# rx_mod-1.net
KiCad netlist of a schematic drawn in EAGLE
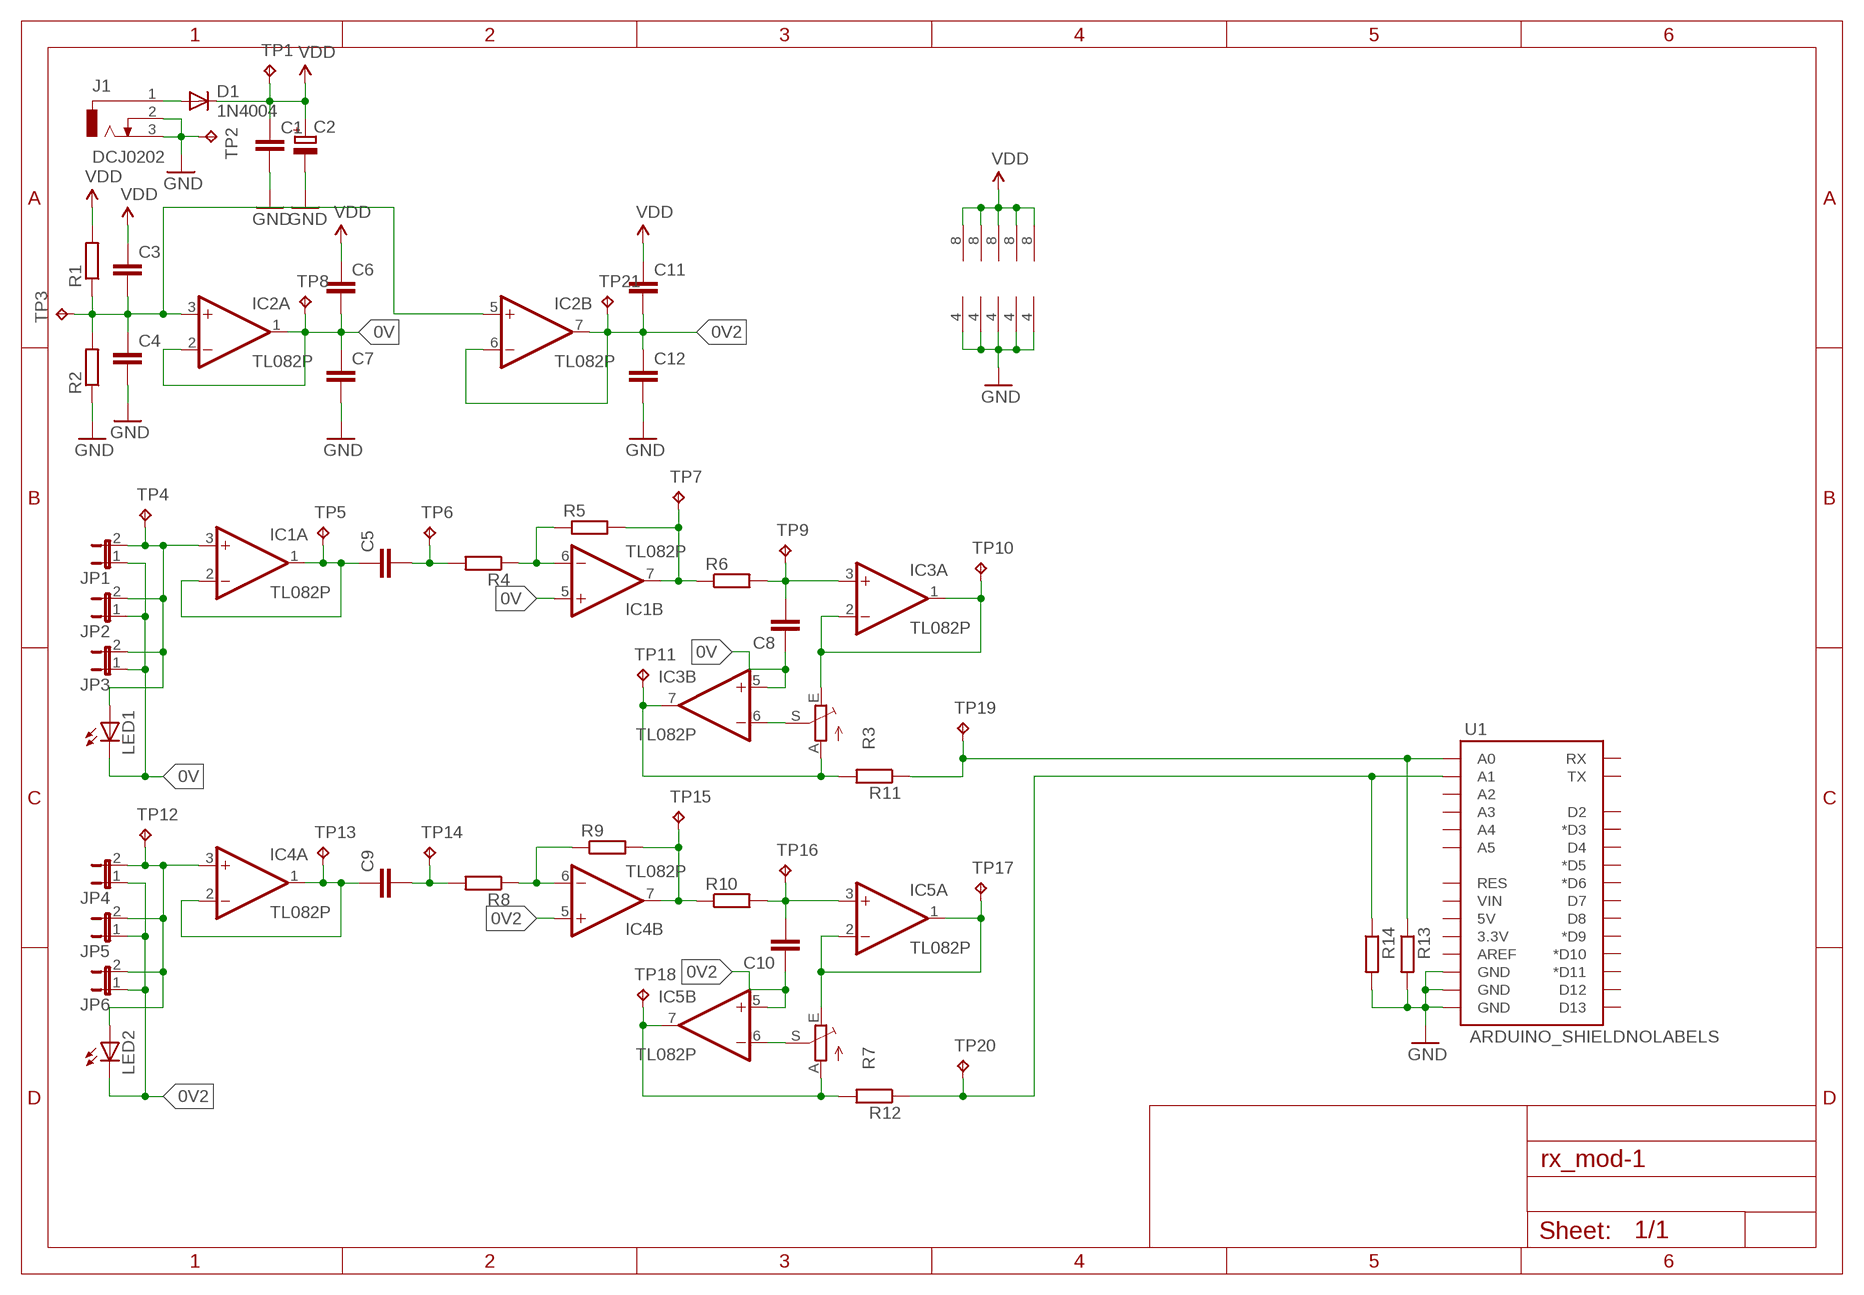
[diagram p0: schematic, sheet 1]

(export (version "E")
  (design (tool "Eeschema 10.0.6"))
  (components
    (comp (ref "C1")
      (value "C-EU050-030X075")
      (footprint "eagle-import:C050-030X075")
      (libsource (lib "eagle-import") (part "C-EU050-030X075"))
    )
    (comp (ref "C2")
      (value "CPOL-EUE2.5-6")
      (footprint "eagle-import:E2,5-6")
      (libsource (lib "eagle-import") (part "CPOL-EUE2.5-6"))
    )
    (comp (ref "C3")
      (value "C-EU050-030X075")
      (footprint "eagle-import:C050-030X075")
      (libsource (lib "eagle-import") (part "C-EU050-030X075"))
    )
    (comp (ref "C4")
      (value "C-EU050-030X075")
      (footprint "eagle-import:C050-030X075")
      (libsource (lib "eagle-import") (part "C-EU050-030X075"))
    )
    (comp (ref "C5")
      (value "C-EU050-030X075")
      (footprint "eagle-import:C050-030X075")
      (libsource (lib "eagle-import") (part "C-EU050-030X075"))
    )
    (comp (ref "C6")
      (value "C-EU050-030X075")
      (footprint "eagle-import:C050-030X075")
      (libsource (lib "eagle-import") (part "C-EU050-030X075"))
    )
    (comp (ref "C7")
      (value "C-EU050-030X075")
      (footprint "eagle-import:C050-030X075")
      (libsource (lib "eagle-import") (part "C-EU050-030X075"))
    )
    (comp (ref "C8")
      (value "C-EU050-030X075")
      (footprint "eagle-import:C050-030X075")
      (libsource (lib "eagle-import") (part "C-EU050-030X075"))
    )
    (comp (ref "C9")
      (value "C-EU050-030X075")
      (footprint "eagle-import:C050-030X075")
      (libsource (lib "eagle-import") (part "C-EU050-030X075"))
    )
    (comp (ref "C10")
      (value "C-EU050-030X075")
      (footprint "eagle-import:C050-030X075")
      (libsource (lib "eagle-import") (part "C-EU050-030X075"))
    )
    (comp (ref "C11")
      (value "C-EU050-030X075")
      (footprint "eagle-import:C050-030X075")
      (libsource (lib "eagle-import") (part "C-EU050-030X075"))
    )
    (comp (ref "C12")
      (value "C-EU050-030X075")
      (footprint "eagle-import:C050-030X075")
      (libsource (lib "eagle-import") (part "C-EU050-030X075"))
    )
    (comp (ref "D1")
      (value "1N4004")
      (footprint "eagle-import:DO41-10")
      (libsource (lib "eagle-import") (part "1N4004"))
    )
    (comp (ref "IC1")
      (value "TL082P")
      (footprint "eagle-import:DIL08")
      (libsource (lib "eagle-import") (part "TL082P"))
    )
    (comp (ref "IC2")
      (value "TL082P")
      (footprint "eagle-import:DIL08")
      (libsource (lib "eagle-import") (part "TL082P"))
    )
    (comp (ref "IC3")
      (value "TL082P")
      (footprint "eagle-import:DIL08")
      (libsource (lib "eagle-import") (part "TL082P"))
    )
    (comp (ref "IC4")
      (value "TL082P")
      (footprint "eagle-import:DIL08")
      (libsource (lib "eagle-import") (part "TL082P"))
    )
    (comp (ref "IC5")
      (value "TL082P")
      (footprint "eagle-import:DIL08")
      (libsource (lib "eagle-import") (part "TL082P"))
    )
    (comp (ref "J1")
      (value "DCJ0202")
      (footprint "eagle-import:DCJ0202")
      (libsource (lib "eagle-import") (part "DCJ0202"))
    )
    (comp (ref "JP1")
      (value "JP1E")
      (footprint "eagle-import:JP1")
      (libsource (lib "eagle-import") (part "JP1E"))
    )
    (comp (ref "JP2")
      (value "JP1E")
      (footprint "eagle-import:JP1")
      (libsource (lib "eagle-import") (part "JP1E"))
    )
    (comp (ref "JP3")
      (value "JP1E")
      (footprint "eagle-import:JP1")
      (libsource (lib "eagle-import") (part "JP1E"))
    )
    (comp (ref "JP4")
      (value "JP1E")
      (footprint "eagle-import:JP1")
      (libsource (lib "eagle-import") (part "JP1E"))
    )
    (comp (ref "JP5")
      (value "JP1E")
      (footprint "eagle-import:JP1")
      (libsource (lib "eagle-import") (part "JP1E"))
    )
    (comp (ref "JP6")
      (value "JP1E")
      (footprint "eagle-import:JP1")
      (libsource (lib "eagle-import") (part "JP1E"))
    )
    (comp (ref "LED1")
      (value "LED5MM")
      (footprint "eagle-import:LED5MM")
      (libsource (lib "eagle-import") (part "LED5MM"))
    )
    (comp (ref "LED2")
      (value "LED5MM")
      (footprint "eagle-import:LED5MM")
      (libsource (lib "eagle-import") (part "LED5MM"))
    )
    (comp (ref "R1")
      (value "R-EU_0207/10")
      (footprint "eagle-import:0207_10")
      (libsource (lib "eagle-import") (part "R-EU_0207/10"))
    )
    (comp (ref "R2")
      (value "R-EU_0207/10")
      (footprint "eagle-import:0207_10")
      (libsource (lib "eagle-import") (part "R-EU_0207/10"))
    )
    (comp (ref "R3")
      (value "TRIM_EU-CA9V")
      (footprint "eagle-import:CA9V")
      (libsource (lib "eagle-import") (part "TRIM_EU-CA9V"))
    )
    (comp (ref "R4")
      (value "R-EU_0207/10")
      (footprint "eagle-import:0207_10")
      (libsource (lib "eagle-import") (part "R-EU_0207/10"))
    )
    (comp (ref "R5")
      (value "R-EU_0207/2V")
      (footprint "eagle-import:0207_2V")
      (libsource (lib "eagle-import") (part "R-EU_0207/2V"))
    )
    (comp (ref "R6")
      (value "R-EU_0207/2V")
      (footprint "eagle-import:0207_2V")
      (libsource (lib "eagle-import") (part "R-EU_0207/2V"))
    )
    (comp (ref "R7")
      (value "TRIM_EU-CA9V")
      (footprint "eagle-import:CA9V")
      (libsource (lib "eagle-import") (part "TRIM_EU-CA9V"))
    )
    (comp (ref "R8")
      (value "R-EU_0207/10")
      (footprint "eagle-import:0207_10")
      (libsource (lib "eagle-import") (part "R-EU_0207/10"))
    )
    (comp (ref "R9")
      (value "R-EU_0207/2V")
      (footprint "eagle-import:0207_2V")
      (libsource (lib "eagle-import") (part "R-EU_0207/2V"))
    )
    (comp (ref "R10")
      (value "R-EU_0207/2V")
      (footprint "eagle-import:0207_2V")
      (libsource (lib "eagle-import") (part "R-EU_0207/2V"))
    )
    (comp (ref "R11")
      (value "R-EU_0207/10")
      (footprint "eagle-import:0207_10")
      (libsource (lib "eagle-import") (part "R-EU_0207/10"))
    )
    (comp (ref "R12")
      (value "R-EU_0207/10")
      (footprint "eagle-import:0207_10")
      (libsource (lib "eagle-import") (part "R-EU_0207/10"))
    )
    (comp (ref "R13")
      (value "R-EU_0207/10")
      (footprint "eagle-import:0207_10")
      (libsource (lib "eagle-import") (part "R-EU_0207/10"))
    )
    (comp (ref "R14")
      (value "R-EU_0207/10")
      (footprint "eagle-import:0207_10")
      (libsource (lib "eagle-import") (part "R-EU_0207/10"))
    )
    (comp (ref "TP1")
      (value "TPPAD1-13")
      (footprint "eagle-import:P1-13")
      (libsource (lib "eagle-import") (part "TPPAD1-13"))
    )
    (comp (ref "TP2")
      (value "TPPAD1-13")
      (footprint "eagle-import:P1-13")
      (libsource (lib "eagle-import") (part "TPPAD1-13"))
    )
    (comp (ref "TP3")
      (value "TPPAD1-13")
      (footprint "eagle-import:P1-13")
      (libsource (lib "eagle-import") (part "TPPAD1-13"))
    )
    (comp (ref "TP4")
      (value "TPPAD1-13")
      (footprint "eagle-import:P1-13")
      (libsource (lib "eagle-import") (part "TPPAD1-13"))
    )
    (comp (ref "TP5")
      (value "TPPAD1-13")
      (footprint "eagle-import:P1-13")
      (libsource (lib "eagle-import") (part "TPPAD1-13"))
    )
    (comp (ref "TP6")
      (value "TPPAD1-13")
      (footprint "eagle-import:P1-13")
      (libsource (lib "eagle-import") (part "TPPAD1-13"))
    )
    (comp (ref "TP7")
      (value "TPPAD1-13")
      (footprint "eagle-import:P1-13")
      (libsource (lib "eagle-import") (part "TPPAD1-13"))
    )
    (comp (ref "TP8")
      (value "TPPAD1-13")
      (footprint "eagle-import:P1-13")
      (libsource (lib "eagle-import") (part "TPPAD1-13"))
    )
    (comp (ref "TP9")
      (value "TPPAD1-13")
      (footprint "eagle-import:P1-13")
      (libsource (lib "eagle-import") (part "TPPAD1-13"))
    )
    (comp (ref "TP10")
      (value "TPPAD1-13")
      (footprint "eagle-import:P1-13")
      (libsource (lib "eagle-import") (part "TPPAD1-13"))
    )
    (comp (ref "TP11")
      (value "TPPAD1-13")
      (footprint "eagle-import:P1-13")
      (libsource (lib "eagle-import") (part "TPPAD1-13"))
    )
    (comp (ref "TP12")
      (value "TPPAD1-13")
      (footprint "eagle-import:P1-13")
      (libsource (lib "eagle-import") (part "TPPAD1-13"))
    )
    (comp (ref "TP13")
      (value "TPPAD1-13")
      (footprint "eagle-import:P1-13")
      (libsource (lib "eagle-import") (part "TPPAD1-13"))
    )
    (comp (ref "TP14")
      (value "TPPAD1-13")
      (footprint "eagle-import:P1-13")
      (libsource (lib "eagle-import") (part "TPPAD1-13"))
    )
    (comp (ref "TP15")
      (value "TPPAD1-13")
      (footprint "eagle-import:P1-13")
      (libsource (lib "eagle-import") (part "TPPAD1-13"))
    )
    (comp (ref "TP16")
      (value "TPPAD1-13")
      (footprint "eagle-import:P1-13")
      (libsource (lib "eagle-import") (part "TPPAD1-13"))
    )
    (comp (ref "TP17")
      (value "TPPAD1-13")
      (footprint "eagle-import:P1-13")
      (libsource (lib "eagle-import") (part "TPPAD1-13"))
    )
    (comp (ref "TP18")
      (value "TPPAD1-13")
      (footprint "eagle-import:P1-13")
      (libsource (lib "eagle-import") (part "TPPAD1-13"))
    )
    (comp (ref "TP19")
      (value "TPPAD1-13")
      (footprint "eagle-import:P1-13")
      (libsource (lib "eagle-import") (part "TPPAD1-13"))
    )
    (comp (ref "TP20")
      (value "TPPAD1-13")
      (footprint "eagle-import:P1-13")
      (libsource (lib "eagle-import") (part "TPPAD1-13"))
    )
    (comp (ref "TP21")
      (value "TPPAD1-13")
      (footprint "eagle-import:P1-13")
      (libsource (lib "eagle-import") (part "TPPAD1-13"))
    )
    (comp (ref "U1")
      (value "ARDUINO_SHIELDNOLABELS")
      (footprint "eagle-import:DUEMILANOVE_SHIELD_NOLABELS")
      (libsource (lib "eagle-import") (part "ARDUINO_SHIELDNOLABELS"))
    )
  )
  (nets
    (net (code "1") (name "0V") (class "Default")
      (node (ref "C6") (pin "2") (pinfunction "2_2") (pintype "passive"))
      (node (ref "C7") (pin "1") (pinfunction "1_1") (pintype "passive"))
      (node (ref "C8") (pin "1") (pinfunction "1_1") (pintype "passive"))
      (node (ref "IC1") (pin "5") (pinfunction "+IN_5") (pintype "input"))
      (node (ref "IC2") (pin "1") (pinfunction "OUT_1") (pintype "output"))
      (node (ref "IC2") (pin "2") (pinfunction "-IN_2") (pintype "input"))
      (node (ref "IC3") (pin "5") (pinfunction "+IN_5") (pintype "input"))
      (node (ref "JP1") (pin "1") (pinfunction "1_1") (pintype "passive"))
      (node (ref "JP2") (pin "1") (pinfunction "1_1") (pintype "passive"))
      (node (ref "JP3") (pin "1") (pinfunction "1_1") (pintype "passive"))
      (node (ref "LED1") (pin "K") (pinfunction "C_K") (pintype "passive"))
      (node (ref "TP8") (pin "TP") (pinfunction "TP_TP") (pintype "input"))
    )
    (net (code "2") (name "0V2") (class "Default")
      (node (ref "C10") (pin "1") (pinfunction "1_1") (pintype "passive"))
      (node (ref "C11") (pin "2") (pinfunction "2_2") (pintype "passive"))
      (node (ref "C12") (pin "1") (pinfunction "1_1") (pintype "passive"))
      (node (ref "IC2") (pin "6") (pinfunction "-IN_6") (pintype "input"))
      (node (ref "IC2") (pin "7") (pinfunction "OUT_7") (pintype "output"))
      (node (ref "IC4") (pin "5") (pinfunction "+IN_5") (pintype "input"))
      (node (ref "IC5") (pin "5") (pinfunction "+IN_5") (pintype "input"))
      (node (ref "JP4") (pin "1") (pinfunction "1_1") (pintype "passive"))
      (node (ref "JP5") (pin "1") (pinfunction "1_1") (pintype "passive"))
      (node (ref "JP6") (pin "1") (pinfunction "1_1") (pintype "passive"))
      (node (ref "LED2") (pin "K") (pinfunction "C_K") (pintype "passive"))
      (node (ref "TP21") (pin "TP") (pinfunction "TP_TP") (pintype "input"))
    )
    (net (code "3") (name "GND") (class "Default")
      (node (ref "C1") (pin "2") (pinfunction "2_2") (pintype "passive"))
      (node (ref "C12") (pin "2") (pinfunction "2_2") (pintype "passive"))
      (node (ref "C2") (pin "-") (pinfunction "-_-") (pintype "passive"))
      (node (ref "C4") (pin "2") (pinfunction "2_2") (pintype "passive"))
      (node (ref "C7") (pin "2") (pinfunction "2_2") (pintype "passive"))
      (node (ref "IC1") (pin "4") (pinfunction "V-_4") (pintype "power_in"))
      (node (ref "IC2") (pin "4") (pinfunction "V-_4") (pintype "power_in"))
      (node (ref "IC3") (pin "4") (pinfunction "V-_4") (pintype "power_in"))
      (node (ref "IC4") (pin "4") (pinfunction "V-_4") (pintype "power_in"))
      (node (ref "IC5") (pin "4") (pinfunction "V-_4") (pintype "power_in"))
      (node (ref "J1") (pin "2") (pinfunction "2_2") (pintype "passive"))
      (node (ref "J1") (pin "3") (pinfunction "3_3") (pintype "passive"))
      (node (ref "R13") (pin "2") (pinfunction "2_2") (pintype "passive"))
      (node (ref "R14") (pin "2") (pinfunction "2_2") (pintype "passive"))
      (node (ref "R2") (pin "1") (pinfunction "1_1") (pintype "passive"))
      (node (ref "TP2") (pin "TP") (pinfunction "TP_TP") (pintype "input"))
      (node (ref "U1") (pin "GND@0") (pinfunction "GND_GND@0") (pintype "bidirectional"))
      (node (ref "U1") (pin "GND@1") (pinfunction "GND_GND@1") (pintype "bidirectional"))
      (node (ref "U1") (pin "GND@2") (pinfunction "GND_GND@2") (pintype "bidirectional"))
    )
    (net (code "4") (name "Net-(C5-Pad2)") (class "Default")
      (node (ref "C5") (pin "2") (pinfunction "2_2") (pintype "passive"))
      (node (ref "R4") (pin "2") (pinfunction "2_2") (pintype "passive"))
      (node (ref "TP6") (pin "TP") (pinfunction "TP_TP") (pintype "input"))
    )
    (net (code "5") (name "Net-(C9-Pad2)") (class "Default")
      (node (ref "C9") (pin "2") (pinfunction "2_2") (pintype "passive"))
      (node (ref "R8") (pin "2") (pinfunction "2_2") (pintype "passive"))
      (node (ref "TP14") (pin "TP") (pinfunction "TP_TP") (pintype "input"))
    )
    (net (code "6") (name "Net-(D1-PadA)") (class "Default")
      (node (ref "D1") (pin "A") (pinfunction "A_A") (pintype "passive"))
      (node (ref "J1") (pin "1") (pinfunction "1_1") (pintype "passive"))
    )
    (net (code "7") (name "Net-(IC1A-+IN)") (class "Default")
      (node (ref "IC1") (pin "3") (pinfunction "+IN_3") (pintype "input"))
      (node (ref "JP1") (pin "2") (pinfunction "2_2") (pintype "passive"))
      (node (ref "JP2") (pin "2") (pinfunction "2_2") (pintype "passive"))
      (node (ref "JP3") (pin "2") (pinfunction "2_2") (pintype "passive"))
      (node (ref "LED1") (pin "A") (pinfunction "A_A") (pintype "passive"))
      (node (ref "TP4") (pin "TP") (pinfunction "TP_TP") (pintype "input"))
    )
    (net (code "8") (name "Net-(IC1A--IN)") (class "Default")
      (node (ref "C5") (pin "1") (pinfunction "1_1") (pintype "passive"))
      (node (ref "IC1") (pin "1") (pinfunction "OUT_1") (pintype "output"))
      (node (ref "IC1") (pin "2") (pinfunction "-IN_2") (pintype "input"))
      (node (ref "TP5") (pin "TP") (pinfunction "TP_TP") (pintype "input"))
    )
    (net (code "9") (name "Net-(IC1B--IN)") (class "Default")
      (node (ref "IC1") (pin "6") (pinfunction "-IN_6") (pintype "input"))
      (node (ref "R4") (pin "1") (pinfunction "1_1") (pintype "passive"))
      (node (ref "R5") (pin "1") (pinfunction "1_1") (pintype "passive"))
    )
    (net (code "10") (name "Net-(IC1B-OUT)") (class "Default")
      (node (ref "IC1") (pin "7") (pinfunction "OUT_7") (pintype "output"))
      (node (ref "R5") (pin "2") (pinfunction "2_2") (pintype "passive"))
      (node (ref "R6") (pin "1") (pinfunction "1_1") (pintype "passive"))
      (node (ref "TP7") (pin "TP") (pinfunction "TP_TP") (pintype "input"))
    )
    (net (code "11") (name "Net-(IC2A-+IN)") (class "Default")
      (node (ref "C3") (pin "2") (pinfunction "2_2") (pintype "passive"))
      (node (ref "C4") (pin "1") (pinfunction "1_1") (pintype "passive"))
      (node (ref "IC2") (pin "3") (pinfunction "+IN_3") (pintype "input"))
      (node (ref "IC2") (pin "5") (pinfunction "+IN_5") (pintype "input"))
      (node (ref "R1") (pin "1") (pinfunction "1_1") (pintype "passive"))
      (node (ref "R2") (pin "2") (pinfunction "2_2") (pintype "passive"))
      (node (ref "TP3") (pin "TP") (pinfunction "TP_TP") (pintype "input"))
    )
    (net (code "12") (name "Net-(IC3A-+IN)") (class "Default")
      (node (ref "C8") (pin "2") (pinfunction "2_2") (pintype "passive"))
      (node (ref "IC3") (pin "3") (pinfunction "+IN_3") (pintype "input"))
      (node (ref "R6") (pin "2") (pinfunction "2_2") (pintype "passive"))
      (node (ref "TP9") (pin "TP") (pinfunction "TP_TP") (pintype "input"))
    )
    (net (code "13") (name "Net-(IC3A--IN)") (class "Default")
      (node (ref "IC3") (pin "1") (pinfunction "OUT_1") (pintype "output"))
      (node (ref "IC3") (pin "2") (pinfunction "-IN_2") (pintype "input"))
      (node (ref "R3") (pin "E") (pinfunction "E_E") (pintype "passive"))
      (node (ref "TP10") (pin "TP") (pinfunction "TP_TP") (pintype "input"))
    )
    (net (code "14") (name "Net-(IC3B--IN)") (class "Default")
      (node (ref "IC3") (pin "6") (pinfunction "-IN_6") (pintype "input"))
      (node (ref "R3") (pin "S") (pinfunction "S_S") (pintype "passive"))
    )
    (net (code "15") (name "Net-(IC3B-OUT)") (class "Default")
      (node (ref "IC3") (pin "7") (pinfunction "OUT_7") (pintype "output"))
      (node (ref "R11") (pin "2") (pinfunction "2_2") (pintype "passive"))
      (node (ref "R3") (pin "A") (pinfunction "A_A") (pintype "passive"))
      (node (ref "TP11") (pin "TP") (pinfunction "TP_TP") (pintype "input"))
    )
    (net (code "16") (name "Net-(IC4A-+IN)") (class "Default")
      (node (ref "IC4") (pin "3") (pinfunction "+IN_3") (pintype "input"))
      (node (ref "JP4") (pin "2") (pinfunction "2_2") (pintype "passive"))
      (node (ref "JP5") (pin "2") (pinfunction "2_2") (pintype "passive"))
      (node (ref "JP6") (pin "2") (pinfunction "2_2") (pintype "passive"))
      (node (ref "LED2") (pin "A") (pinfunction "A_A") (pintype "passive"))
      (node (ref "TP12") (pin "TP") (pinfunction "TP_TP") (pintype "input"))
    )
    (net (code "17") (name "Net-(IC4A--IN)") (class "Default")
      (node (ref "C9") (pin "1") (pinfunction "1_1") (pintype "passive"))
      (node (ref "IC4") (pin "1") (pinfunction "OUT_1") (pintype "output"))
      (node (ref "IC4") (pin "2") (pinfunction "-IN_2") (pintype "input"))
      (node (ref "TP13") (pin "TP") (pinfunction "TP_TP") (pintype "input"))
    )
    (net (code "18") (name "Net-(IC4B--IN)") (class "Default")
      (node (ref "IC4") (pin "6") (pinfunction "-IN_6") (pintype "input"))
      (node (ref "R8") (pin "1") (pinfunction "1_1") (pintype "passive"))
      (node (ref "R9") (pin "1") (pinfunction "1_1") (pintype "passive"))
    )
    (net (code "19") (name "Net-(IC4B-OUT)") (class "Default")
      (node (ref "IC4") (pin "7") (pinfunction "OUT_7") (pintype "output"))
      (node (ref "R10") (pin "1") (pinfunction "1_1") (pintype "passive"))
      (node (ref "R9") (pin "2") (pinfunction "2_2") (pintype "passive"))
      (node (ref "TP15") (pin "TP") (pinfunction "TP_TP") (pintype "input"))
    )
    (net (code "20") (name "Net-(IC5A-+IN)") (class "Default")
      (node (ref "C10") (pin "2") (pinfunction "2_2") (pintype "passive"))
      (node (ref "IC5") (pin "3") (pinfunction "+IN_3") (pintype "input"))
      (node (ref "R10") (pin "2") (pinfunction "2_2") (pintype "passive"))
      (node (ref "TP16") (pin "TP") (pinfunction "TP_TP") (pintype "input"))
    )
    (net (code "21") (name "Net-(IC5A--IN)") (class "Default")
      (node (ref "IC5") (pin "1") (pinfunction "OUT_1") (pintype "output"))
      (node (ref "IC5") (pin "2") (pinfunction "-IN_2") (pintype "input"))
      (node (ref "R7") (pin "E") (pinfunction "E_E") (pintype "passive"))
      (node (ref "TP17") (pin "TP") (pinfunction "TP_TP") (pintype "input"))
    )
    (net (code "22") (name "Net-(IC5B--IN)") (class "Default")
      (node (ref "IC5") (pin "6") (pinfunction "-IN_6") (pintype "input"))
      (node (ref "R7") (pin "S") (pinfunction "S_S") (pintype "passive"))
    )
    (net (code "23") (name "Net-(IC5B-OUT)") (class "Default")
      (node (ref "IC5") (pin "7") (pinfunction "OUT_7") (pintype "output"))
      (node (ref "R12") (pin "2") (pinfunction "2_2") (pintype "passive"))
      (node (ref "R7") (pin "A") (pinfunction "A_A") (pintype "passive"))
      (node (ref "TP18") (pin "TP") (pinfunction "TP_TP") (pintype "input"))
    )
    (net (code "24") (name "Net-(R11-Pad1)") (class "Default")
      (node (ref "R11") (pin "1") (pinfunction "1_1") (pintype "passive"))
      (node (ref "R13") (pin "1") (pinfunction "1_1") (pintype "passive"))
      (node (ref "TP19") (pin "TP") (pinfunction "TP_TP") (pintype "input"))
      (node (ref "U1") (pin "A0") (pinfunction "A0_A0") (pintype "bidirectional"))
    )
    (net (code "25") (name "Net-(R12-Pad1)") (class "Default")
      (node (ref "R12") (pin "1") (pinfunction "1_1") (pintype "passive"))
      (node (ref "R14") (pin "1") (pinfunction "1_1") (pintype "passive"))
      (node (ref "TP20") (pin "TP") (pinfunction "TP_TP") (pintype "input"))
      (node (ref "U1") (pin "A1") (pinfunction "A1_A1") (pintype "bidirectional"))
    )
    (net (code "26") (name "VDD") (class "Default")
      (node (ref "C1") (pin "1") (pinfunction "1_1") (pintype "passive"))
      (node (ref "C11") (pin "1") (pinfunction "1_1") (pintype "passive"))
      (node (ref "C2") (pin "+") (pinfunction "+_+") (pintype "passive"))
      (node (ref "C3") (pin "1") (pinfunction "1_1") (pintype "passive"))
      (node (ref "C6") (pin "1") (pinfunction "1_1") (pintype "passive"))
      (node (ref "D1") (pin "C") (pinfunction "C_C") (pintype "passive"))
      (node (ref "IC1") (pin "8") (pinfunction "V+_8") (pintype "power_in"))
      (node (ref "IC2") (pin "8") (pinfunction "V+_8") (pintype "power_in"))
      (node (ref "IC3") (pin "8") (pinfunction "V+_8") (pintype "power_in"))
      (node (ref "IC4") (pin "8") (pinfunction "V+_8") (pintype "power_in"))
      (node (ref "IC5") (pin "8") (pinfunction "V+_8") (pintype "power_in"))
      (node (ref "R1") (pin "2") (pinfunction "2_2") (pintype "passive"))
      (node (ref "TP1") (pin "TP") (pinfunction "TP_TP") (pintype "input"))
    )
    (net (code "27") (name "unconnected-(U1-*D3-PadD3)") (class "Default")
      (node (ref "U1") (pin "D3") (pinfunction "*D3_D3") (pintype "bidirectional"))
    )
    (net (code "28") (name "unconnected-(U1-*D5-PadD5)") (class "Default")
      (node (ref "U1") (pin "D5") (pinfunction "*D5_D5") (pintype "bidirectional"))
    )
    (net (code "29") (name "unconnected-(U1-*D6-PadD6)") (class "Default")
      (node (ref "U1") (pin "D6") (pinfunction "*D6_D6") (pintype "bidirectional"))
    )
    (net (code "30") (name "unconnected-(U1-*D9-PadD9)") (class "Default")
      (node (ref "U1") (pin "D9") (pinfunction "*D9_D9") (pintype "bidirectional"))
    )
    (net (code "31") (name "unconnected-(U1-*D10-PadD10)") (class "Default")
      (node (ref "U1") (pin "D10") (pinfunction "*D10_D10") (pintype "bidirectional"))
    )
    (net (code "32") (name "unconnected-(U1-*D11-PadD11)") (class "Default")
      (node (ref "U1") (pin "D11") (pinfunction "*D11_D11") (pintype "bidirectional"))
    )
    (net (code "33") (name "unconnected-(U1-Pad3.3V)") (class "Default")
      (node (ref "U1") (pin "3.3V") (pinfunction "3.3V_3.3V") (pintype "bidirectional"))
    )
    (net (code "34") (name "unconnected-(U1-Pad5V)") (class "Default")
      (node (ref "U1") (pin "5V") (pinfunction "5V_5V") (pintype "bidirectional"))
    )
    (net (code "35") (name "unconnected-(U1-PadA2)") (class "Default")
      (node (ref "U1") (pin "A2") (pinfunction "A2_A2") (pintype "bidirectional"))
    )
    (net (code "36") (name "unconnected-(U1-PadA3)") (class "Default")
      (node (ref "U1") (pin "A3") (pinfunction "A3_A3") (pintype "bidirectional"))
    )
    (net (code "37") (name "unconnected-(U1-PadA4)") (class "Default")
      (node (ref "U1") (pin "A4") (pinfunction "A4_A4") (pintype "bidirectional"))
    )
    (net (code "38") (name "unconnected-(U1-PadA5)") (class "Default")
      (node (ref "U1") (pin "A5") (pinfunction "A5_A5") (pintype "bidirectional"))
    )
    (net (code "39") (name "unconnected-(U1-PadAREF)") (class "Default")
      (node (ref "U1") (pin "AREF") (pinfunction "AREF_AREF") (pintype "bidirectional"))
    )
    (net (code "40") (name "unconnected-(U1-PadD2)") (class "Default")
      (node (ref "U1") (pin "D2") (pinfunction "D2_D2") (pintype "bidirectional"))
    )
    (net (code "41") (name "unconnected-(U1-PadD4)") (class "Default")
      (node (ref "U1") (pin "D4") (pinfunction "D4_D4") (pintype "bidirectional"))
    )
    (net (code "42") (name "unconnected-(U1-PadD7)") (class "Default")
      (node (ref "U1") (pin "D7") (pinfunction "D7_D7") (pintype "bidirectional"))
    )
    (net (code "43") (name "unconnected-(U1-PadD8)") (class "Default")
      (node (ref "U1") (pin "D8") (pinfunction "D8_D8") (pintype "bidirectional"))
    )
    (net (code "44") (name "unconnected-(U1-PadD12)") (class "Default")
      (node (ref "U1") (pin "D12") (pinfunction "D12_D12") (pintype "bidirectional"))
    )
    (net (code "45") (name "unconnected-(U1-PadD13)") (class "Default")
      (node (ref "U1") (pin "D13") (pinfunction "D13_D13") (pintype "bidirectional"))
    )
    (net (code "46") (name "unconnected-(U1-PadRES)") (class "Default")
      (node (ref "U1") (pin "RES") (pinfunction "RES_RES") (pintype "bidirectional"))
    )
    (net (code "47") (name "unconnected-(U1-PadRX)") (class "Default")
      (node (ref "U1") (pin "RX") (pinfunction "RX_RX") (pintype "bidirectional"))
    )
    (net (code "48") (name "unconnected-(U1-PadTX)") (class "Default")
      (node (ref "U1") (pin "TX") (pinfunction "TX_TX") (pintype "bidirectional"))
    )
    (net (code "49") (name "unconnected-(U1-PadVIN)") (class "Default")
      (node (ref "U1") (pin "VIN") (pinfunction "VIN_VIN") (pintype "bidirectional"))
    )
  )
)
